# SFP.net
KiCad netlist of a schematic drawn in Altium Designer
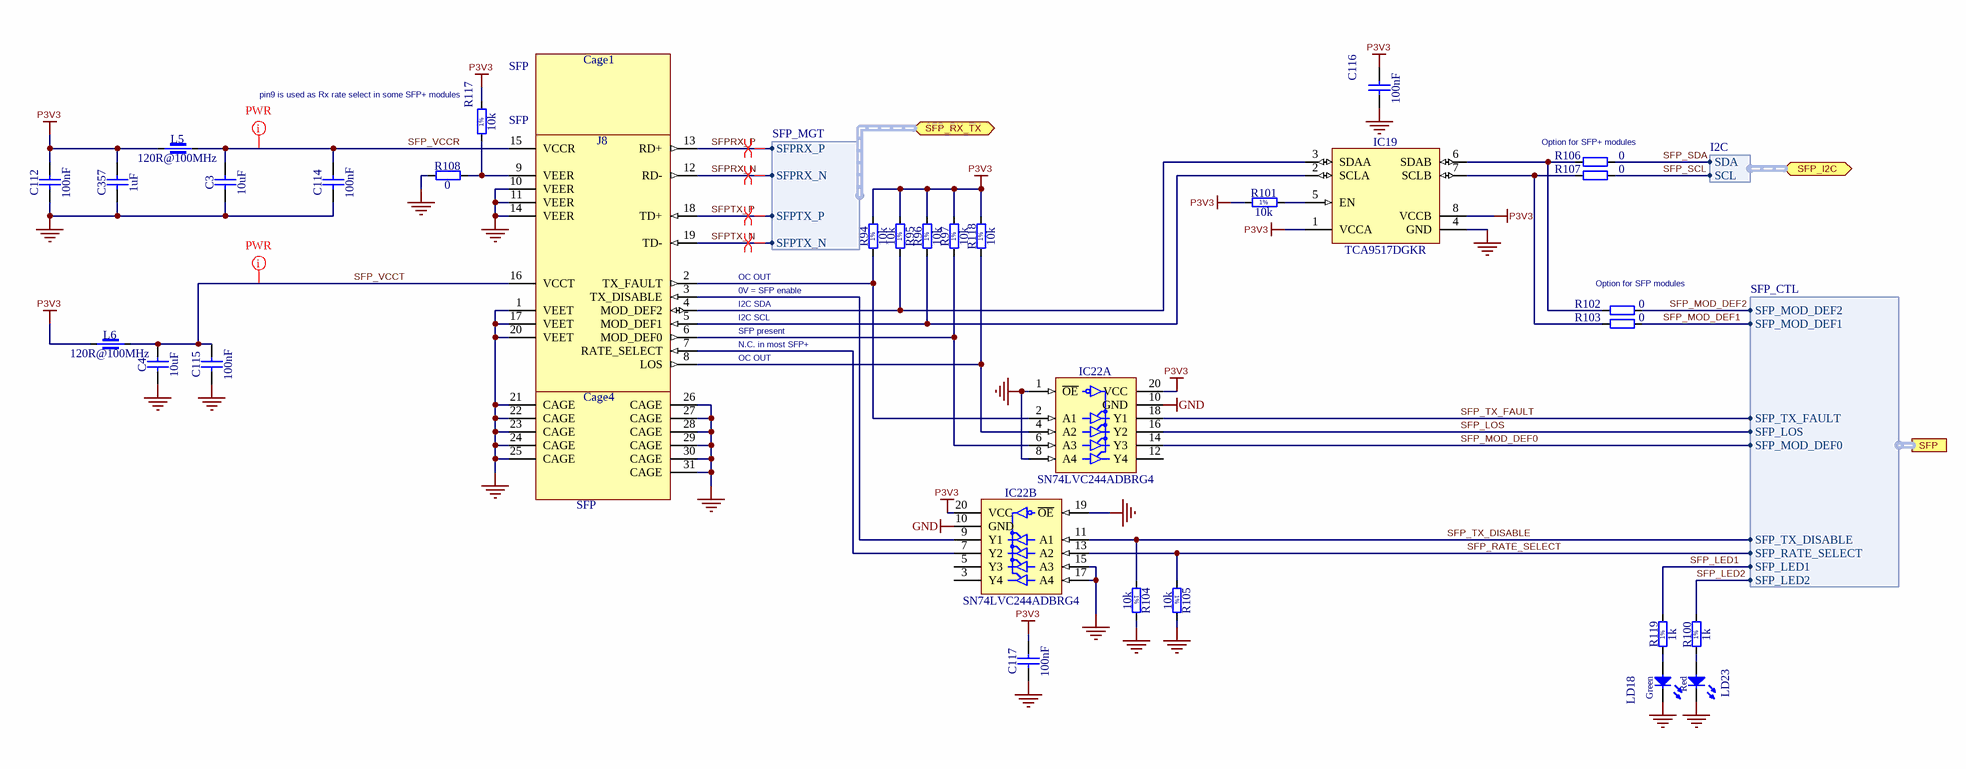
[diagram p0: SFP.SchDoc]

(export (version "E")
  (design (tool "Eeschema 10.0.6"))
  (components
    (comp (ref "C3")
      (value "10uF")
      (footprint "CAPC1608X87N")
      (description "Non-polarised capacitor")
      (fields
        (field (name "MANUFACTURER PART NUMBER") "CC0603_10uF_6.3V_20%_X5R")
        (field (name "MANUFACTURER") "GENERIC")
        (field (name "AUTHOR") "CERN DEM JLC")
      )
      (libsource (lib "Capacitors") (part "Capacitor - non polarized"))
    )
    (comp (ref "C4")
      (value "10uF")
      (footprint "CAPC1608X87N")
      (description "Non-polarised capacitor")
      (fields
        (field (name "MANUFACTURER PART NUMBER") "CC0603_10uF_6.3V_20%_X5R")
        (field (name "MANUFACTURER") "GENERIC")
        (field (name "AUTHOR") "CERN DEM JLC")
      )
      (libsource (lib "Capacitors") (part "Capacitor - non polarized"))
    )
    (comp (ref "C112")
      (value "100nF")
      (footprint "CAPC0603X33N")
      (description "Non-polarised capacitor")
      (fields
        (field (name "MANUFACTURER PART NUMBER") "CC0201_100NF_6.3V_10%_X5R")
        (field (name "MANUFACTURER") "GENERIC")
        (field (name "AUTHOR") "CERN DEM JLC")
      )
      (libsource (lib "Capacitors") (part "Capacitor - non polarized"))
    )
    (comp (ref "C114")
      (value "100nF")
      (footprint "CAPC0603X33N")
      (description "Non-polarised capacitor")
      (fields
        (field (name "MANUFACTURER PART NUMBER") "CC0201_100NF_6.3V_10%_X5R")
        (field (name "MANUFACTURER") "GENERIC")
        (field (name "AUTHOR") "CERN DEM JLC")
      )
      (libsource (lib "Capacitors") (part "Capacitor - non polarized"))
    )
    (comp (ref "C115")
      (value "100nF")
      (footprint "CAPC0603X33N")
      (description "Non-polarised capacitor")
      (fields
        (field (name "MANUFACTURER PART NUMBER") "CC0201_100NF_6.3V_10%_X5R")
        (field (name "MANUFACTURER") "GENERIC")
        (field (name "AUTHOR") "CERN DEM JLC")
      )
      (libsource (lib "Capacitors") (part "Capacitor - non polarized"))
    )
    (comp (ref "C116")
      (value "100nF")
      (footprint "CAPC0603X33N")
      (description "Non-polarised capacitor")
      (fields
        (field (name "MANUFACTURER PART NUMBER") "CC0201_100NF_6.3V_10%_X5R")
        (field (name "MANUFACTURER") "GENERIC")
        (field (name "AUTHOR") "CERN DEM JLC")
      )
      (libsource (lib "Capacitors") (part "Capacitor - non polarized"))
    )
    (comp (ref "C117")
      (value "100nF")
      (footprint "CAPC0603X33N")
      (description "Non-polarised capacitor")
      (fields
        (field (name "MANUFACTURER PART NUMBER") "CC0201_100NF_6.3V_10%_X5R")
        (field (name "MANUFACTURER") "GENERIC")
        (field (name "AUTHOR") "CERN DEM JLC")
      )
      (libsource (lib "Capacitors") (part "Capacitor - non polarized"))
    )
    (comp (ref "C357")
      (value "1uF")
      (footprint "CAPC1005X55N")
      (description "Non-polarised capacitor")
      (fields
        (field (name "MANUFACTURER PART NUMBER") "CC0402_1UF_16V_10%_X5R")
        (field (name "MANUFACTURER") "GENERIC")
        (field (name "AUTHOR") "CERN DEM JLC")
      )
      (libsource (lib "Capacitors") (part "Capacitor - non polarized"))
    )
    (comp (ref "Cage1")
      (value "SFP")
      (footprint "TYCO_6367035-1")
      (description "SFP  Cage Top (Small Form-factor Pluggable)")
      (fields
        (field (name "MANUFACTURER PART NUMBER") "6367035-1")
        (field (name "MANUFACTURER") "TYCO ELECTRONICS")
        (field (name "AUTHOR") "CERN DEM JLC")
      )
      (libsource (lib "Connectors") (part "SFPx1_Cage Top"))
    )
    (comp (ref "Cage4")
      (value "SFP")
      (footprint "TYCO_6367034-1")
      (description "SFP  Cage Bottom (Small Form-factor Pluggable)")
      (fields
        (field (name "MANUFACTURER PART NUMBER") "6367034-1")
        (field (name "MANUFACTURER") "TYCO ELECTRONICS")
        (field (name "AUTHOR") "CERN DEM JLC")
      )
      (libsource (lib "Connectors") (part "SFPx1_Cage Bottom"))
    )
    (comp (ref "IC19")
      (value "TCA9517DGKR")
      (footprint "SOP65P490X110-8N")
      (description "Level-Translating I2C Bus Repeater")
      (fields (field (name "MANUFACTURER") "TEXAS INSTRUMENTS") (field (name "AUTHOR") "CERN DEM JLC"))
      (libsource (lib "ICs And Semiconductors") (part "TCA9517"))
    )
    (comp (ref "IC22")
      (value "SN74LVC244ADBRG4")
      (footprint "SOP65P780X200-20N")
      (description "Octal Buffer/Driver with 3-State Ouputs")
      (fields (field (name "MANUFACTURER") "TEXAS INSTRUMENTS") (field (name "AUTHOR") "CERN DEM JMW"))
      (libsource (lib "ICs And Semiconductors") (part "74244_a"))
    )
    (comp (ref "J8")
      (value "SFP")
      (footprint "TYCO_1367073-1")
      (description "20 Position SFP  Connector (Small Form-factor Pluggable)")
      (fields
        (field (name "MANUFACTURER PART NUMBER") "1367073-1")
        (field (name "MANUFACTURER") "TYCO ELECTRONICS")
        (field (name "AUTHOR") "CERN DEM JLC")
      )
      (libsource (lib "Connectors") (part "SFPx1"))
    )
    (comp (ref "L5")
      (value "120R@100MHz")
      (footprint "INDC1608X65N")
      (fields
        (field (name "MANUFACTURER PART NUMBER") "BLM18SG121TN1D")
        (field (name "MANUFACTURER") "MURATA")
        (field (name "PART NUMBER") "IND0603_MURATA_BLM18SG121TN1D")
        (field (name "AUTHOR") "CERN DEM JLC")
      )
      (libsource (lib "Inductors & Transformers") (part "Ferrite Bead"))
    )
    (comp (ref "L6")
      (value "120R@100MHz")
      (footprint "INDC1608X65N")
      (fields
        (field (name "MANUFACTURER PART NUMBER") "BLM18SG121TN1D")
        (field (name "MANUFACTURER") "MURATA")
        (field (name "PART NUMBER") "IND0603_MURATA_BLM18SG121TN1D")
        (field (name "AUTHOR") "CERN DEM JLC")
      )
      (libsource (lib "Inductors & Transformers") (part "Ferrite Bead"))
    )
    (comp (ref "LD18")
      (value "Green")
      (footprint "LED_AVAGO_HSME-C120")
      (description "LED Green 1C 2A")
      (fields
        (field (name "MANUFACTURER PART NUMBER") "HSME-C120")
        (field (name "MANUFACTURER") "AVAGO TECHNOLOGIES")
        (field (name "AUTHOR") "CERN DEM JMW")
      )
      (libsource (lib "ICs And Semiconductors") (part "LED Green 1C 2A"))
    )
    (comp (ref "LD23")
      (value "Red")
      (footprint "LED_AVAGO_HSMC-C120")
      (description "LED Red 1C 2A")
      (fields
        (field (name "MANUFACTURER PART NUMBER") "HSMC-C120")
        (field (name "MANUFACTURER") "AVAGO TECHNOLOGIES")
        (field (name "AUTHOR") "CERN DEM JMW")
      )
      (libsource (lib "ICs And Semiconductors") (part "LED Red 1C 2A"))
    )
    (comp (ref "R94")
      (value "10k")
      (footprint "RESC1005X40N")
      (description "Resistor - 1%")
      (fields
        (field (name "MANUFACTURER PART NUMBER") "R0402_10K_1%_0.0625W_100PPM")
        (field (name "MANUFACTURER") "GENERIC")
        (field (name "AUTHOR") "CERN DEM JLC")
      )
      (libsource (lib "Resistors") (part "Resistor - 1%"))
    )
    (comp (ref "R95")
      (value "10k")
      (footprint "RESC1005X40N")
      (description "Resistor - 1%")
      (fields
        (field (name "MANUFACTURER PART NUMBER") "R0402_10K_1%_0.0625W_100PPM")
        (field (name "MANUFACTURER") "GENERIC")
        (field (name "AUTHOR") "CERN DEM JLC")
      )
      (libsource (lib "Resistors") (part "Resistor - 1%"))
    )
    (comp (ref "R96")
      (value "10k")
      (footprint "RESC1005X40N")
      (description "Resistor - 1%")
      (fields
        (field (name "MANUFACTURER PART NUMBER") "R0402_10K_1%_0.0625W_100PPM")
        (field (name "MANUFACTURER") "GENERIC")
        (field (name "AUTHOR") "CERN DEM JLC")
      )
      (libsource (lib "Resistors") (part "Resistor - 1%"))
    )
    (comp (ref "R97")
      (value "10k")
      (footprint "RESC1005X40N")
      (description "Resistor - 1%")
      (fields
        (field (name "MANUFACTURER PART NUMBER") "R0402_10K_1%_0.0625W_100PPM")
        (field (name "MANUFACTURER") "GENERIC")
        (field (name "AUTHOR") "CERN DEM JLC")
      )
      (libsource (lib "Resistors") (part "Resistor - 1%"))
    )
    (comp (ref "R100")
      (value "1k")
      (footprint "RESC1005X40N")
      (description "Resistor - 1%")
      (fields
        (field (name "MANUFACTURER PART NUMBER") "R0402_1K_1%_0.0625W_100PPM")
        (field (name "MANUFACTURER") "GENERIC")
        (field (name "AUTHOR") "CERN DEM JLC")
      )
      (libsource (lib "Resistors") (part "Resistor - 1%"))
    )
    (comp (ref "R101")
      (value "10k")
      (footprint "RESC1005X40N")
      (description "Resistor - 1%")
      (fields
        (field (name "MANUFACTURER PART NUMBER") "R0402_10K_1%_0.0625W_100PPM")
        (field (name "MANUFACTURER") "GENERIC")
        (field (name "AUTHOR") "CERN DEM JLC")
      )
      (libsource (lib "Resistors") (part "Resistor - 1%"))
    )
    (comp (ref "R102")
      (value "0")
      (footprint "RESC1005X40N")
      (description "Resistor")
      (fields
        (field (name "MANUFACTURER PART NUMBER") "R0402_0R_JUMPER")
        (field (name "MANUFACTURER") "GENERIC")
        (field (name "AUTHOR") "CERN DEM JLC")
      )
      (libsource (lib "Resistors") (part "Resistor"))
    )
    (comp (ref "R103")
      (value "0")
      (footprint "RESC1005X40N")
      (description "Resistor")
      (fields
        (field (name "MANUFACTURER PART NUMBER") "R0402_0R_JUMPER")
        (field (name "MANUFACTURER") "GENERIC")
        (field (name "AUTHOR") "CERN DEM JLC")
      )
      (libsource (lib "Resistors") (part "Resistor"))
    )
    (comp (ref "R104")
      (value "10k")
      (footprint "RESC1005X40N")
      (description "Resistor - 1%")
      (fields
        (field (name "MANUFACTURER PART NUMBER") "R0402_10K_1%_0.0625W_100PPM")
        (field (name "MANUFACTURER") "GENERIC")
        (field (name "AUTHOR") "CERN DEM JLC")
      )
      (libsource (lib "Resistors") (part "Resistor - 1%"))
    )
    (comp (ref "R105")
      (value "10k")
      (footprint "RESC1005X40N")
      (description "Resistor - 1%")
      (fields
        (field (name "MANUFACTURER PART NUMBER") "R0402_10K_1%_0.0625W_100PPM")
        (field (name "MANUFACTURER") "GENERIC")
        (field (name "AUTHOR") "CERN DEM JLC")
      )
      (libsource (lib "Resistors") (part "Resistor - 1%"))
    )
    (comp (ref "R106")
      (value "0")
      (footprint "RESC1005X40N")
      (description "Resistor")
      (fields
        (field (name "MANUFACTURER PART NUMBER") "R0402_0R_JUMPER")
        (field (name "MANUFACTURER") "GENERIC")
        (field (name "AUTHOR") "CERN DEM JLC")
      )
      (libsource (lib "Resistors") (part "Resistor"))
    )
    (comp (ref "R107")
      (value "0")
      (footprint "RESC1005X40N")
      (description "Resistor")
      (fields
        (field (name "MANUFACTURER PART NUMBER") "R0402_0R_JUMPER")
        (field (name "MANUFACTURER") "GENERIC")
        (field (name "AUTHOR") "CERN DEM JLC")
      )
      (libsource (lib "Resistors") (part "Resistor"))
    )
    (comp (ref "R108")
      (value "0")
      (footprint "RESC1005X40N")
      (description "Resistor")
      (fields
        (field (name "MANUFACTURER PART NUMBER") "R0402_0R_JUMPER")
        (field (name "MANUFACTURER") "GENERIC")
        (field (name "AUTHOR") "CERN DEM JLC")
      )
      (libsource (lib "Resistors") (part "Resistor"))
    )
    (comp (ref "R117")
      (value "10k")
      (footprint "RESC1005X40N")
      (description "Resistor - 1%")
      (fields
        (field (name "MANUFACTURER PART NUMBER") "R0402_10K_1%_0.0625W_100PPM")
        (field (name "MANUFACTURER") "GENERIC")
        (field (name "AUTHOR") "CERN DEM JLC")
      )
      (libsource (lib "Resistors") (part "Resistor - 1%"))
    )
    (comp (ref "R118")
      (value "10k")
      (footprint "RESC1005X40N")
      (description "Resistor - 1%")
      (fields
        (field (name "MANUFACTURER PART NUMBER") "R0402_10K_1%_0.0625W_100PPM")
        (field (name "MANUFACTURER") "GENERIC")
        (field (name "AUTHOR") "CERN DEM JLC")
      )
      (libsource (lib "Resistors") (part "Resistor - 1%"))
    )
    (comp (ref "R119")
      (value "1k")
      (footprint "RESC1005X40N")
      (description "Resistor - 1%")
      (fields
        (field (name "MANUFACTURER PART NUMBER") "R0402_1K_1%_0.0625W_100PPM")
        (field (name "MANUFACTURER") "GENERIC")
        (field (name "AUTHOR") "CERN DEM JLC")
      )
      (libsource (lib "Resistors") (part "Resistor - 1%"))
    )
  )
  (nets
    (net (code "4") (name "/SFPRX_N") (class "Default")
      (node (ref "J8") (pin "12") (pinfunction "RD-_12") (pintype "output"))
    )
    (net (code "5") (name "/SFPRX_P") (class "Default")
      (node (ref "J8") (pin "13") (pinfunction "RD+_13") (pintype "output"))
    )
    (net (code "6") (name "/SFPTX_N") (class "Default")
      (node (ref "J8") (pin "19") (pinfunction "TD-_19") (pintype "input"))
    )
    (net (code "7") (name "/SFPTX_P") (class "Default")
      (node (ref "J8") (pin "18") (pinfunction "TD+_18") (pintype "input"))
    )
    (net (code "8") (name "/SFP_LED1") (class "Default")
      (node (ref "R119") (pin "2") (pinfunction "2_2") (pintype "passive"))
    )
    (net (code "9") (name "/SFP_LED2") (class "Default")
      (node (ref "R100") (pin "2") (pinfunction "2_2") (pintype "passive"))
    )
    (net (code "10") (name "/SFP_LOS") (class "Default")
      (node (ref "IC22") (pin "16") (pinfunction "Y2_16") (pintype "tri_state"))
    )
    (net (code "11") (name "/SFP_MOD_DEF0") (class "Default")
      (node (ref "IC22") (pin "14") (pinfunction "Y3_14") (pintype "tri_state"))
    )
    (net (code "12") (name "/SFP_MOD_DEF1") (class "Default")
      (node (ref "R103") (pin "2") (pinfunction "2_2") (pintype "passive"))
    )
    (net (code "13") (name "/SFP_MOD_DEF2") (class "Default")
      (node (ref "R102") (pin "2") (pinfunction "2_2") (pintype "passive"))
    )
    (net (code "14") (name "/SFP_RATE_SELECT") (class "Default")
      (node (ref "IC22") (pin "13") (pinfunction "A2_13") (pintype "input"))
      (node (ref "R105") (pin "1") (pinfunction "1_1") (pintype "passive"))
    )
    (net (code "15") (name "/SFP_SCL") (class "Default")
      (node (ref "R107") (pin "2") (pinfunction "2_2") (pintype "passive"))
    )
    (net (code "16") (name "/SFP_SDA") (class "Default")
      (node (ref "R106") (pin "2") (pinfunction "2_2") (pintype "passive"))
    )
    (net (code "17") (name "/SFP_TX_DISABLE") (class "Default")
      (node (ref "IC22") (pin "11") (pinfunction "A1_11") (pintype "input"))
      (node (ref "R104") (pin "1") (pinfunction "1_1") (pintype "passive"))
    )
    (net (code "18") (name "/SFP_TX_FAULT") (class "Default")
      (node (ref "IC22") (pin "18") (pinfunction "Y1_18") (pintype "tri_state"))
    )
    (net (code "19") (name "/SFP_VCCR") (class "Default")
      (node (ref "C114") (pin "2") (pinfunction "2_2") (pintype "passive"))
      (node (ref "C3") (pin "2") (pinfunction "2_2") (pintype "passive"))
      (node (ref "J8") (pin "15") (pinfunction "VCCR_15") (pintype "power_in"))
      (node (ref "L5") (pin "2") (pinfunction "2_2") (pintype "passive"))
    )
    (net (code "20") (name "/SFP_VCCT") (class "Default")
      (node (ref "C115") (pin "2") (pinfunction "2_2") (pintype "passive"))
      (node (ref "C4") (pin "2") (pinfunction "2_2") (pintype "passive"))
      (node (ref "J8") (pin "16") (pinfunction "VCCT_16") (pintype "power_in"))
      (node (ref "L6") (pin "2") (pinfunction "2_2") (pintype "passive"))
    )
    (net (code "24") (name "GND") (class "Default")
      (node (ref "C112") (pin "1") (pinfunction "1_1") (pintype "passive"))
      (node (ref "C114") (pin "1") (pinfunction "1_1") (pintype "passive"))
      (node (ref "C115") (pin "1") (pinfunction "1_1") (pintype "passive"))
      (node (ref "C116") (pin "1") (pinfunction "1_1") (pintype "passive"))
      (node (ref "C117") (pin "1") (pinfunction "1_1") (pintype "passive"))
      (node (ref "C3") (pin "1") (pinfunction "1_1") (pintype "passive"))
      (node (ref "C357") (pin "1") (pinfunction "1_1") (pintype "passive"))
      (node (ref "C4") (pin "1") (pinfunction "1_1") (pintype "passive"))
      (node (ref "Cage4") (pin "21") (pinfunction "CAGE_21") (pintype "power_in"))
      (node (ref "Cage4") (pin "22") (pinfunction "CAGE_22") (pintype "power_in"))
      (node (ref "Cage4") (pin "23") (pinfunction "CAGE_23") (pintype "power_in"))
      (node (ref "Cage4") (pin "24") (pinfunction "CAGE_24") (pintype "power_in"))
      (node (ref "Cage4") (pin "25") (pinfunction "CAGE_25") (pintype "power_in"))
      (node (ref "Cage4") (pin "26") (pinfunction "CAGE_26") (pintype "power_in"))
      (node (ref "Cage4") (pin "27") (pinfunction "CAGE_27") (pintype "power_in"))
      (node (ref "Cage4") (pin "28") (pinfunction "CAGE_28") (pintype "power_in"))
      (node (ref "Cage4") (pin "29") (pinfunction "CAGE_29") (pintype "power_in"))
      (node (ref "Cage4") (pin "30") (pinfunction "CAGE_30") (pintype "power_in"))
      (node (ref "Cage4") (pin "31") (pinfunction "CAGE_31") (pintype "power_in"))
      (node (ref "IC19") (pin "4") (pinfunction "GND_4") (pintype "power_in"))
      (node (ref "IC22") (pin "1") (pinfunction "~{OE}_1") (pintype "input"))
      (node (ref "IC22") (pin "10") (pinfunction "GND_10") (pintype "power_in"))
      (node (ref "IC22") (pin "15") (pinfunction "A3_15") (pintype "input"))
      (node (ref "IC22") (pin "17") (pinfunction "A4_17") (pintype "input"))
      (node (ref "IC22") (pin "19") (pinfunction "~{OE}_19") (pintype "input"))
      (node (ref "IC22") (pin "8") (pinfunction "A4_8") (pintype "input"))
      (node (ref "J8") (pin "1") (pinfunction "VEET_1") (pintype "power_in"))
      (node (ref "J8") (pin "10") (pinfunction "VEER_10") (pintype "power_in"))
      (node (ref "J8") (pin "11") (pinfunction "VEER_11") (pintype "power_in"))
      (node (ref "J8") (pin "14") (pinfunction "VEER_14") (pintype "power_in"))
      (node (ref "J8") (pin "17") (pinfunction "VEET_17") (pintype "power_in"))
      (node (ref "J8") (pin "20") (pinfunction "VEET_20") (pintype "power_in"))
      (node (ref "LD18") (pin "1") (pinfunction "C_1") (pintype "passive"))
      (node (ref "LD23") (pin "1") (pinfunction "C_1") (pintype "passive"))
      (node (ref "R104") (pin "2") (pinfunction "2_2") (pintype "passive"))
      (node (ref "R105") (pin "2") (pinfunction "2_2") (pintype "passive"))
      (node (ref "R108") (pin "1") (pinfunction "1_1") (pintype "passive"))
    )
    (net (code "25") (name "Net-(IC19-EN)") (class "Default")
      (node (ref "IC19") (pin "5") (pinfunction "EN_5") (pintype "input"))
      (node (ref "R101") (pin "2") (pinfunction "2_2") (pintype "passive"))
    )
    (net (code "26") (name "Net-(IC19-SCLA)") (class "Default")
      (node (ref "IC19") (pin "2") (pinfunction "SCLA_2") (pintype "bidirectional"))
      (node (ref "J8") (pin "5") (pinfunction "MOD_DEF1_5") (pintype "input"))
      (node (ref "R96") (pin "1") (pinfunction "1_1") (pintype "passive"))
    )
    (net (code "27") (name "Net-(IC19-SCLB)") (class "Default")
      (node (ref "IC19") (pin "7") (pinfunction "SCLB_7") (pintype "bidirectional"))
      (node (ref "R103") (pin "1") (pinfunction "1_1") (pintype "passive"))
      (node (ref "R107") (pin "1") (pinfunction "1_1") (pintype "passive"))
    )
    (net (code "28") (name "Net-(IC19-SDAA)") (class "Default")
      (node (ref "IC19") (pin "3") (pinfunction "SDAA_3") (pintype "bidirectional"))
      (node (ref "J8") (pin "4") (pinfunction "MOD_DEF2_4") (pintype "bidirectional"))
      (node (ref "R95") (pin "1") (pinfunction "1_1") (pintype "passive"))
    )
    (net (code "29") (name "Net-(IC19-SDAB)") (class "Default")
      (node (ref "IC19") (pin "6") (pinfunction "SDAB_6") (pintype "bidirectional"))
      (node (ref "R102") (pin "1") (pinfunction "1_1") (pintype "passive"))
      (node (ref "R106") (pin "1") (pinfunction "1_1") (pintype "passive"))
    )
    (net (code "30") (name "Net-(IC22A-A1)") (class "Default")
      (node (ref "IC22") (pin "2") (pinfunction "A1_2") (pintype "input"))
      (node (ref "J8") (pin "2") (pinfunction "TX_FAULT_2") (pintype "output"))
      (node (ref "R94") (pin "1") (pinfunction "1_1") (pintype "passive"))
    )
    (net (code "31") (name "Net-(IC22A-A2)") (class "Default")
      (node (ref "IC22") (pin "4") (pinfunction "A2_4") (pintype "input"))
      (node (ref "J8") (pin "8") (pinfunction "LOS_8") (pintype "output"))
      (node (ref "R118") (pin "1") (pinfunction "1_1") (pintype "passive"))
    )
    (net (code "32") (name "Net-(IC22A-A3)") (class "Default")
      (node (ref "IC22") (pin "6") (pinfunction "A3_6") (pintype "input"))
      (node (ref "J8") (pin "6") (pinfunction "MOD_DEF0_6") (pintype "output"))
      (node (ref "R97") (pin "1") (pinfunction "1_1") (pintype "passive"))
    )
    (net (code "33") (name "Net-(IC22B-Y1)") (class "Default")
      (node (ref "IC22") (pin "9") (pinfunction "Y1_9") (pintype "tri_state"))
      (node (ref "J8") (pin "3") (pinfunction "TX_DISABLE_3") (pintype "input"))
    )
    (net (code "34") (name "Net-(IC22B-Y2)") (class "Default")
      (node (ref "IC22") (pin "7") (pinfunction "Y2_7") (pintype "tri_state"))
      (node (ref "J8") (pin "7") (pinfunction "RATE_SELECT_7") (pintype "input"))
    )
    (net (code "35") (name "Net-(J8-VEER-Pad9)") (class "Default")
      (node (ref "J8") (pin "9") (pinfunction "VEER_9") (pintype "power_in"))
      (node (ref "R108") (pin "2") (pinfunction "2_2") (pintype "passive"))
      (node (ref "R117") (pin "1") (pinfunction "1_1") (pintype "passive"))
    )
    (net (code "36") (name "Net-(LD18-A)") (class "Default")
      (node (ref "LD18") (pin "2") (pinfunction "A_2") (pintype "passive"))
      (node (ref "R119") (pin "1") (pinfunction "1_1") (pintype "passive"))
    )
    (net (code "37") (name "Net-(LD23-A)") (class "Default")
      (node (ref "LD23") (pin "2") (pinfunction "A_2") (pintype "passive"))
      (node (ref "R100") (pin "1") (pinfunction "1_1") (pintype "passive"))
    )
    (net (code "38") (name "P3V3") (class "Default")
      (node (ref "C112") (pin "2") (pinfunction "2_2") (pintype "passive"))
      (node (ref "C116") (pin "2") (pinfunction "2_2") (pintype "passive"))
      (node (ref "C117") (pin "2") (pinfunction "2_2") (pintype "passive"))
      (node (ref "C357") (pin "2") (pinfunction "2_2") (pintype "passive"))
      (node (ref "IC19") (pin "1") (pinfunction "VCCA_1") (pintype "power_in"))
      (node (ref "IC19") (pin "8") (pinfunction "VCCB_8") (pintype "power_in"))
      (node (ref "IC22") (pin "20") (pinfunction "VCC_20") (pintype "power_in"))
      (node (ref "L5") (pin "1") (pinfunction "1_1") (pintype "passive"))
      (node (ref "L6") (pin "1") (pinfunction "1_1") (pintype "passive"))
      (node (ref "R101") (pin "1") (pinfunction "1_1") (pintype "passive"))
      (node (ref "R117") (pin "2") (pinfunction "2_2") (pintype "passive"))
      (node (ref "R118") (pin "2") (pinfunction "2_2") (pintype "passive"))
      (node (ref "R94") (pin "2") (pinfunction "2_2") (pintype "passive"))
      (node (ref "R95") (pin "2") (pinfunction "2_2") (pintype "passive"))
      (node (ref "R96") (pin "2") (pinfunction "2_2") (pintype "passive"))
      (node (ref "R97") (pin "2") (pinfunction "2_2") (pintype "passive"))
    )
    (net (code "39") (name "unconnected-(IC22A-Y4-Pad12)") (class "Default")
      (node (ref "IC22") (pin "12") (pinfunction "Y4_12") (pintype "tri_state"))
    )
    (net (code "40") (name "unconnected-(IC22B-Y3-Pad5)") (class "Default")
      (node (ref "IC22") (pin "5") (pinfunction "Y3_5") (pintype "tri_state"))
    )
    (net (code "41") (name "unconnected-(IC22B-Y4-Pad3)") (class "Default")
      (node (ref "IC22") (pin "3") (pinfunction "Y4_3") (pintype "tri_state"))
    )
  )
)
